# SinglaAntenna.net
KiCad netlist of a schematic drawn in Altium Designer
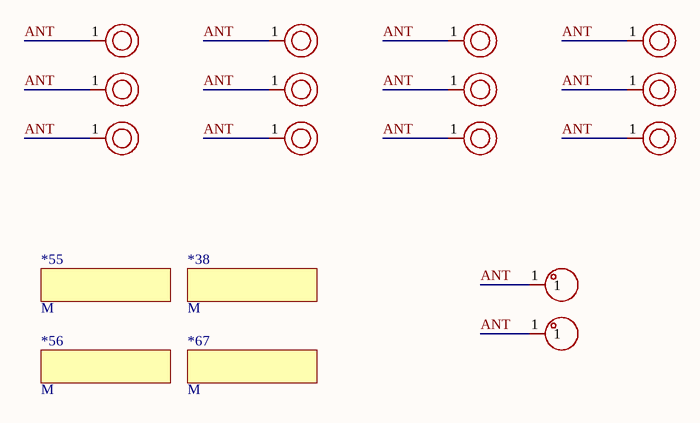
[diagram p0: SinglaAntenna.SchDoc]

(export (version "E")
  (design (tool "Eeschema 10.0.6"))
  (components
    (comp (ref "*38") (value "M") (footprint "PCBComponent_1") (libsource (lib "AntennaMask") (part "M")))
    (comp (ref "*55") (value "M") (footprint "PCBComponent_1") (libsource (lib "AntennaMask") (part "M")))
    (comp (ref "*56") (value "M") (footprint "PCBComponent_1") (libsource (lib "AntennaMask") (part "M")))
    (comp (ref "*67") (value "M") (footprint "PCBComponent_1") (libsource (lib "AntennaMask") (part "M")))
    (comp (ref "PIN60")
      (value "BWCD-L5.0W2.0H2.5")
      (footprint "CONN-SMD_BWCD-L5.0W2.0H2.5")
      (fields (field (name "MANUFACTURER") "BAT WIRELESS(蝙蝠无线)"))
      (libsource (lib "BWCD-L5.0W2.0H2.51_BWCD-L5.0W2.0H2.5") (part "BWCD-L5.0W2.0H2.5"))
    )
    (comp (ref "PIN61")
      (value "BWCD-L5.0W2.0H2.5")
      (footprint "CONN-SMD_BWCD-L5.0W2.0H2.5")
      (fields (field (name "MANUFACTURER") "BAT WIRELESS(蝙蝠无线)"))
      (libsource (lib "BWCD-L5.0W2.0H2.51_BWCD-L5.0W2.0H2.5") (part "BWCD-L5.0W2.0H2.5"))
    )
    (comp (ref "PIN62")
      (value "BWCD-L5.0W2.0H2.5")
      (footprint "CONN-SMD_BWCD-L5.0W2.0H2.5")
      (fields (field (name "MANUFACTURER") "BAT WIRELESS(蝙蝠无线)"))
      (libsource (lib "BWCD-L5.0W2.0H2.51_BWCD-L5.0W2.0H2.5") (part "BWCD-L5.0W2.0H2.5"))
    )
    (comp (ref "PIN63")
      (value "BWCD-L5.0W2.0H2.5")
      (footprint "CONN-SMD_BWCD-L5.0W2.0H2.5")
      (fields (field (name "MANUFACTURER") "BAT WIRELESS(蝙蝠无线)"))
      (libsource (lib "BWCD-L5.0W2.0H2.51_BWCD-L5.0W2.0H2.5") (part "BWCD-L5.0W2.0H2.5"))
    )
    (comp (ref "PIN64")
      (value "BWCD-L5.0W2.0H2.5")
      (footprint "CONN-SMD_BWCD-L5.0W2.0H2.5")
      (fields (field (name "MANUFACTURER") "BAT WIRELESS(蝙蝠无线)"))
      (libsource (lib "BWCD-L5.0W2.0H2.51_BWCD-L5.0W2.0H2.5") (part "BWCD-L5.0W2.0H2.5"))
    )
    (comp (ref "PIN65")
      (value "BWCD-L5.0W2.0H2.5")
      (footprint "CONN-SMD_BWCD-L5.0W2.0H2.5")
      (fields (field (name "MANUFACTURER") "BAT WIRELESS(蝙蝠无线)"))
      (libsource (lib "BWCD-L5.0W2.0H2.51_BWCD-L5.0W2.0H2.5") (part "BWCD-L5.0W2.0H2.5"))
    )
    (comp (ref "PIN66")
      (value "BWCD-L5.0W2.0H2.5")
      (footprint "CONN-SMD_BWCD-L5.0W2.0H2.5")
      (fields (field (name "MANUFACTURER") "BAT WIRELESS(蝙蝠无线)"))
      (libsource (lib "BWCD-L5.0W2.0H2.51_BWCD-L5.0W2.0H2.5") (part "BWCD-L5.0W2.0H2.5"))
    )
    (comp (ref "PIN67")
      (value "BWCD-L5.0W2.0H2.5")
      (footprint "CONN-SMD_BWCD-L5.0W2.0H2.5")
      (fields (field (name "MANUFACTURER") "BAT WIRELESS(蝙蝠无线)"))
      (libsource (lib "BWCD-L5.0W2.0H2.51_BWCD-L5.0W2.0H2.5") (part "BWCD-L5.0W2.0H2.5"))
    )
    (comp (ref "PIN68")
      (value "BWCD-L5.0W2.0H2.5")
      (footprint "CONN-SMD_BWCD-L5.0W2.0H2.5")
      (fields (field (name "MANUFACTURER") "BAT WIRELESS(蝙蝠无线)"))
      (libsource (lib "BWCD-L5.0W2.0H2.51_BWCD-L5.0W2.0H2.5") (part "BWCD-L5.0W2.0H2.5"))
    )
    (comp (ref "PIN69")
      (value "BWCD-L5.0W2.0H2.5")
      (footprint "CONN-SMD_BWCD-L5.0W2.0H2.5")
      (fields (field (name "MANUFACTURER") "BAT WIRELESS(蝙蝠无线)"))
      (libsource (lib "BWCD-L5.0W2.0H2.51_BWCD-L5.0W2.0H2.5") (part "BWCD-L5.0W2.0H2.5"))
    )
    (comp (ref "PIN70")
      (value "BWCD-L5.0W2.0H2.5")
      (footprint "CONN-SMD_BWCD-L5.0W2.0H2.5")
      (fields (field (name "MANUFACTURER") "BAT WIRELESS(蝙蝠无线)"))
      (libsource (lib "BWCD-L5.0W2.0H2.51_BWCD-L5.0W2.0H2.5") (part "BWCD-L5.0W2.0H2.5"))
    )
    (comp (ref "PIN71")
      (value "BWCD-L5.0W2.0H2.5")
      (footprint "CONN-SMD_BWCD-L5.0W2.0H2.5")
      (fields (field (name "MANUFACTURER") "BAT WIRELESS(蝙蝠无线)"))
      (libsource (lib "BWCD-L5.0W2.0H2.51_BWCD-L5.0W2.0H2.5") (part "BWCD-L5.0W2.0H2.5"))
    )
    (comp (ref "U11")
      (value "SMTSO2040CTJ")
      (footprint "SMD_BD5.6-L5.6-W5.6-D3.6")
      (fields (field (name "MANUFACTURER") "Sinhoo(雄和远景)") (field (name "MANUFACTURER PART") "SMTSO2020CTJ"))
      (libsource (lib "SMTSO2020CTJ1_SMTSO2020CTJ") (part "SMTSO2020CTJ"))
    )
    (comp (ref "U12")
      (value "SMTSO2040CTJ")
      (footprint "SMD_BD5.6-L5.6-W5.6-D3.6")
      (fields (field (name "MANUFACTURER") "Sinhoo(雄和远景)") (field (name "MANUFACTURER PART") "SMTSO2020CTJ"))
      (libsource (lib "SMTSO2020CTJ1_SMTSO2020CTJ") (part "SMTSO2020CTJ"))
    )
  )
  (nets
    (net (code "1") (name "/ANT") (class "Default")
      (node (ref "PIN60") (pin "1") (pinfunction "1_1") (pintype "passive"))
      (node (ref "PIN61") (pin "1") (pinfunction "1_1") (pintype "passive"))
      (node (ref "PIN62") (pin "1") (pinfunction "1_1") (pintype "passive"))
      (node (ref "PIN63") (pin "1") (pinfunction "1_1") (pintype "passive"))
      (node (ref "PIN64") (pin "1") (pinfunction "1_1") (pintype "passive"))
      (node (ref "PIN65") (pin "1") (pinfunction "1_1") (pintype "passive"))
      (node (ref "PIN66") (pin "1") (pinfunction "1_1") (pintype "passive"))
      (node (ref "PIN67") (pin "1") (pinfunction "1_1") (pintype "passive"))
      (node (ref "PIN68") (pin "1") (pinfunction "1_1") (pintype "passive"))
      (node (ref "PIN69") (pin "1") (pinfunction "1_1") (pintype "passive"))
      (node (ref "PIN70") (pin "1") (pinfunction "1_1") (pintype "passive"))
      (node (ref "PIN71") (pin "1") (pinfunction "1_1") (pintype "passive"))
      (node (ref "U11") (pin "1") (pinfunction "1_1") (pintype "passive"))
      (node (ref "U12") (pin "1") (pinfunction "1_1") (pintype "passive"))
    )
  )
)
